# 02_ZYNQ_CORE_POS.net
KiCad netlist of a schematic drawn in Altium Designer
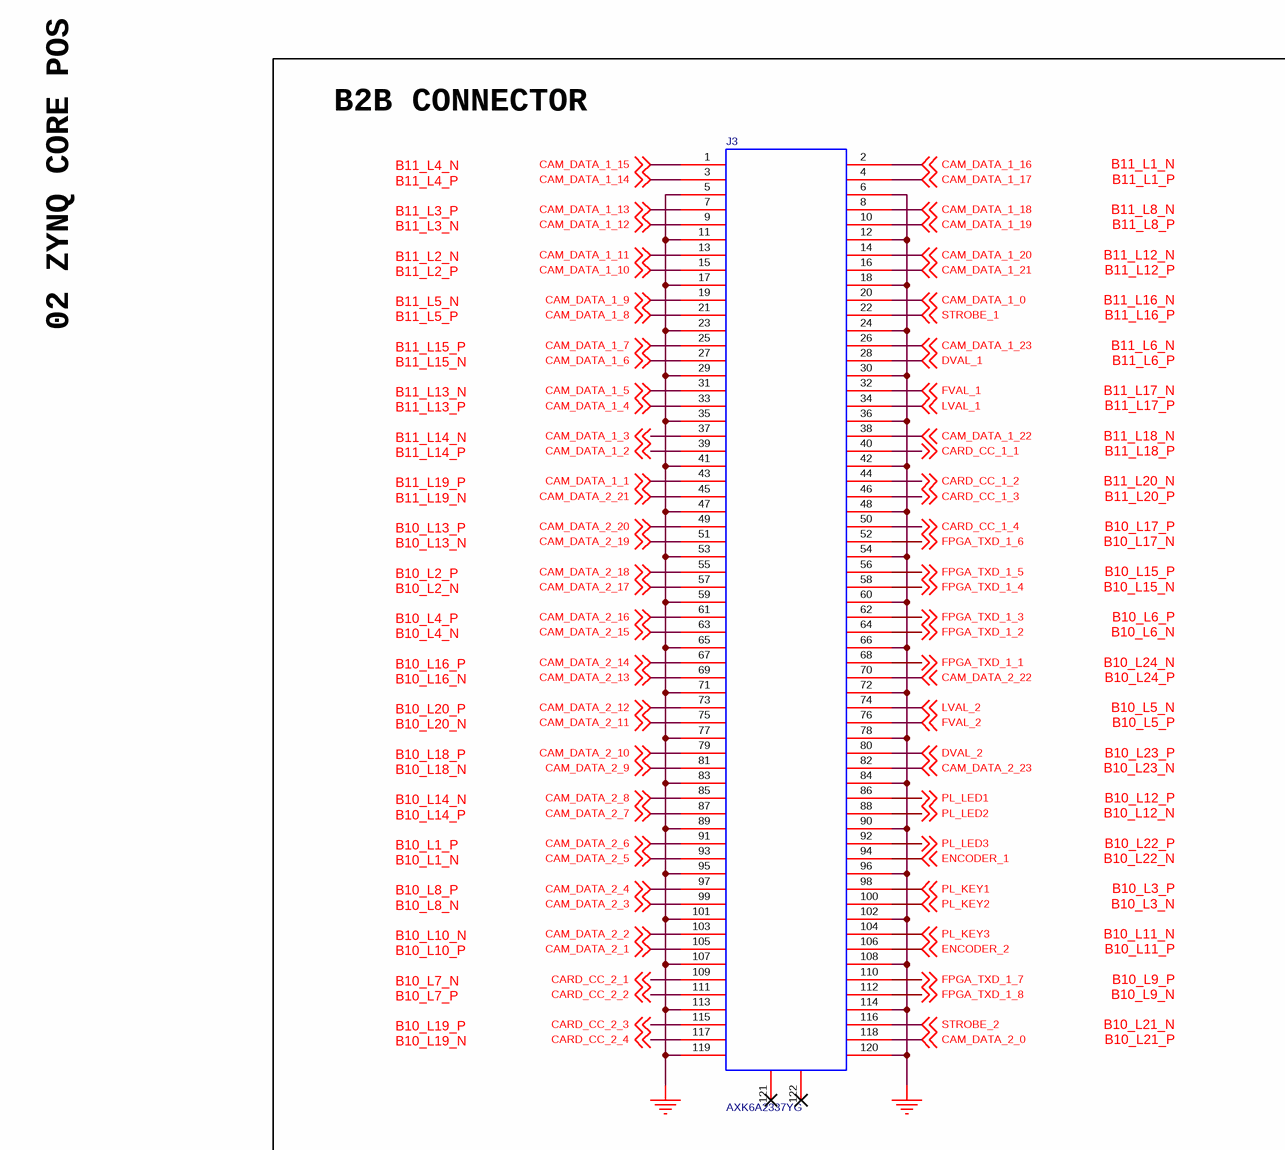
[diagram p0: 02_ZYNQ_CORE_POS.SchDoc, top left]
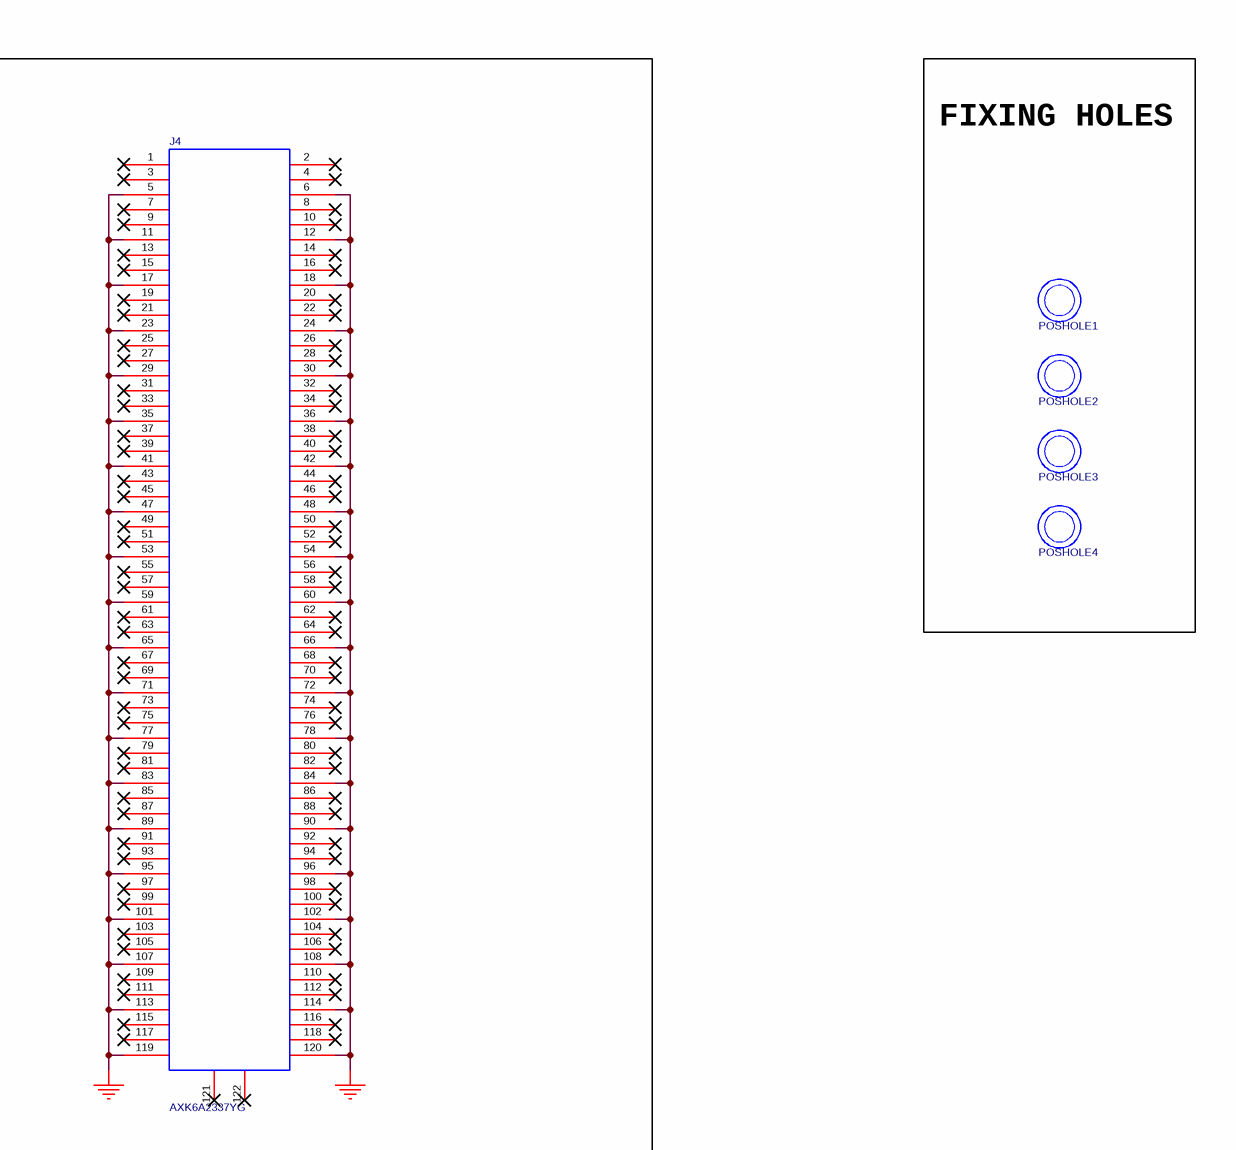
[diagram p1: 02_ZYNQ_CORE_POS.SchDoc, top right]
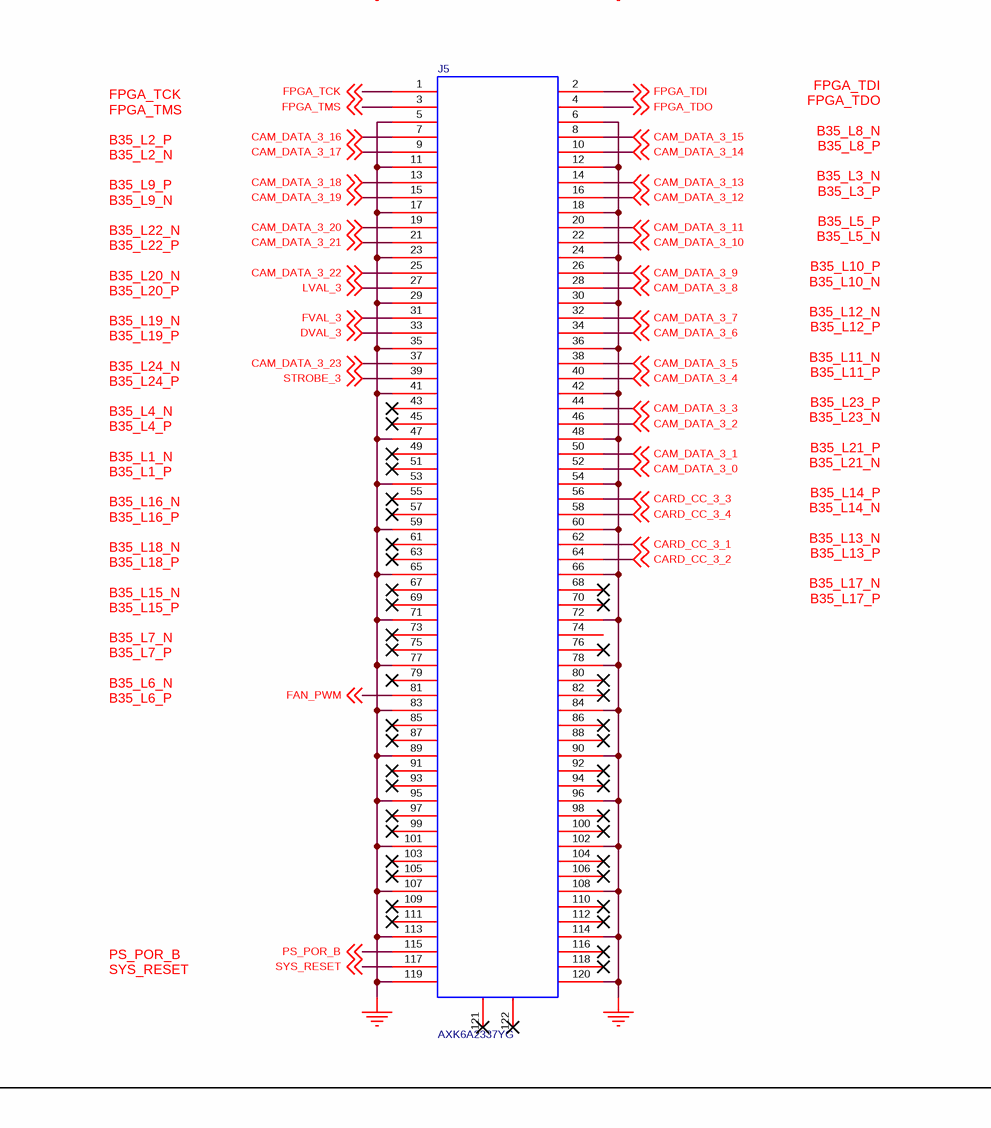
[diagram p2: 02_ZYNQ_CORE_POS.SchDoc, bottom left]
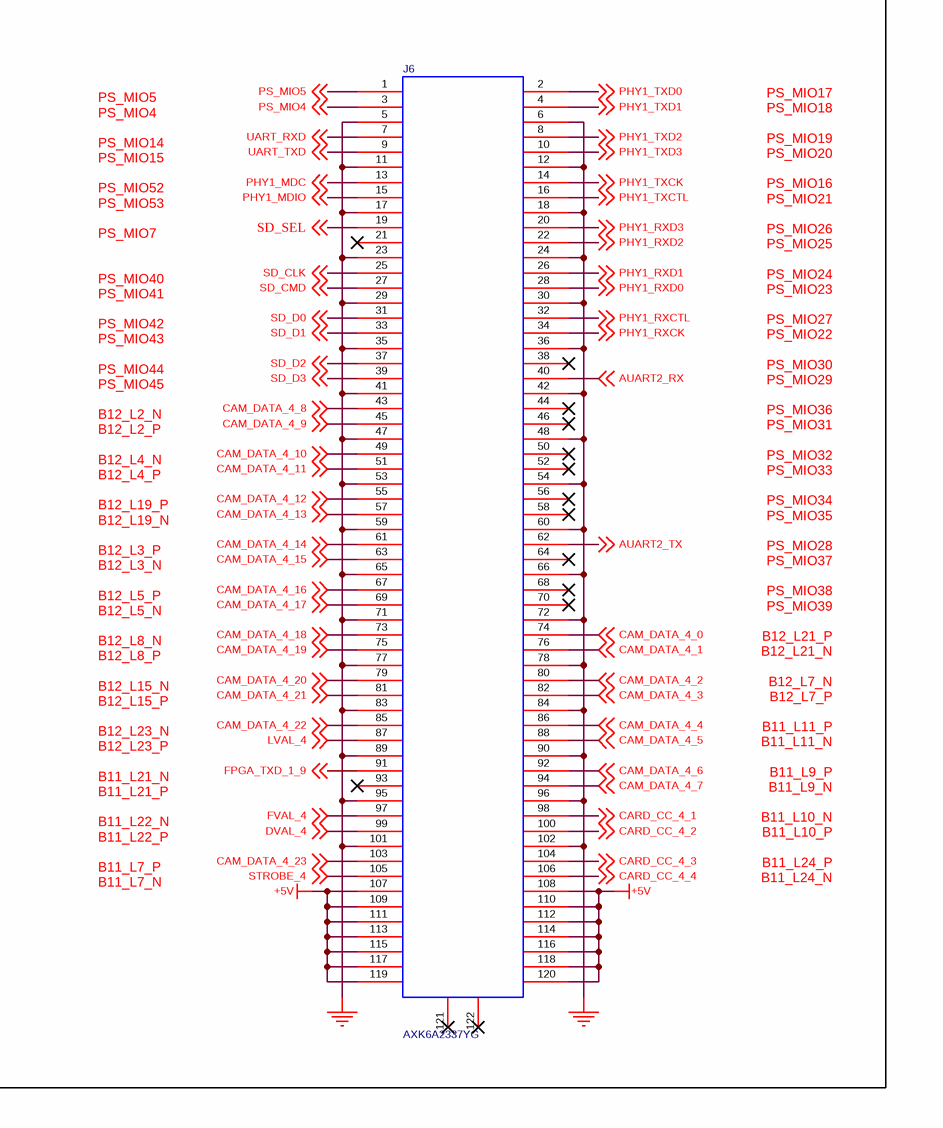
[diagram p3: 02_ZYNQ_CORE_POS.SchDoc, bottom right]

(export (version "E")
  (design (tool "Eeschema 10.0.6"))
  (components
    (comp (ref "J3")
      (value "AXK6A2337YG")
      (footprint "zynq:AXK620337YG")
      (libsource (lib "zynq") (part "120pin"))
    )
    (comp (ref "J4")
      (value "AXK6A2337YG")
      (footprint "zynq:AXK620337YG")
      (libsource (lib "zynq") (part "120pin"))
    )
    (comp (ref "J5")
      (value "AXK6A2337YG")
      (footprint "zynq:AXK620337YG")
      (libsource (lib "zynq") (part "120pin"))
    )
    (comp (ref "J6")
      (value "AXK6A2337YG")
      (footprint "zynq:AXK620337YG")
      (libsource (lib "zynq") (part "120pin"))
    )
    (comp (ref "POSHOLE1")
      (value "POSHOLE")
      (footprint "zynq:POSHOLE-3.2")
      (libsource (lib "zynq") (part "POSHOLE"))
    )
    (comp (ref "POSHOLE2")
      (value "POSHOLE")
      (footprint "zynq:POSHOLE-3.2")
      (libsource (lib "zynq") (part "POSHOLE"))
    )
    (comp (ref "POSHOLE3")
      (value "POSHOLE")
      (footprint "zynq:POSHOLE-3.2")
      (libsource (lib "zynq") (part "POSHOLE"))
    )
    (comp (ref "POSHOLE4")
      (value "POSHOLE")
      (footprint "zynq:POSHOLE-3.2")
      (libsource (lib "zynq") (part "POSHOLE"))
    )
  )
  (nets
    (net (code "1") (name "+5V") (class "Default")
      (node (ref "J6") (pin "107") (pintype "passive"))
      (node (ref "J6") (pin "108") (pintype "passive"))
      (node (ref "J6") (pin "109") (pintype "passive"))
      (node (ref "J6") (pin "110") (pintype "passive"))
      (node (ref "J6") (pin "111") (pintype "passive"))
      (node (ref "J6") (pin "112") (pintype "passive"))
      (node (ref "J6") (pin "113") (pintype "passive"))
      (node (ref "J6") (pin "114") (pintype "passive"))
      (node (ref "J6") (pin "115") (pintype "passive"))
      (node (ref "J6") (pin "116") (pintype "passive"))
      (node (ref "J6") (pin "117") (pintype "passive"))
      (node (ref "J6") (pin "118") (pintype "passive"))
      (node (ref "J6") (pin "119") (pintype "passive"))
      (node (ref "J6") (pin "120") (pintype "passive"))
    )
    (net (code "2") (name "AUART2_RX") (class "Default") (node (ref "J6") (pin "40") (pintype "passive")))
    (net (code "3") (name "AUART2_TX") (class "Default") (node (ref "J6") (pin "62") (pintype "passive")))
    (net (code "4") (name "CAM_DATA_1_0") (class "Default") (node (ref "J3") (pin "20") (pintype "passive")))
    (net (code "5") (name "CAM_DATA_1_1") (class "Default") (node (ref "J3") (pin "43") (pintype "passive")))
    (net (code "6") (name "CAM_DATA_1_2") (class "Default") (node (ref "J3") (pin "39") (pintype "passive")))
    (net (code "7") (name "CAM_DATA_1_3") (class "Default") (node (ref "J3") (pin "37") (pintype "passive")))
    (net (code "8") (name "CAM_DATA_1_4") (class "Default") (node (ref "J3") (pin "33") (pintype "passive")))
    (net (code "9") (name "CAM_DATA_1_5") (class "Default") (node (ref "J3") (pin "31") (pintype "passive")))
    (net (code "10") (name "CAM_DATA_1_6") (class "Default") (node (ref "J3") (pin "27") (pintype "passive")))
    (net (code "11") (name "CAM_DATA_1_7") (class "Default") (node (ref "J3") (pin "25") (pintype "passive")))
    (net (code "12") (name "CAM_DATA_1_8") (class "Default") (node (ref "J3") (pin "21") (pintype "passive")))
    (net (code "13") (name "CAM_DATA_1_9") (class "Default") (node (ref "J3") (pin "19") (pintype "passive")))
    (net (code "14") (name "CAM_DATA_1_10") (class "Default")
      (node (ref "J3") (pin "15") (pintype "passive"))
    )
    (net (code "15") (name "CAM_DATA_1_11") (class "Default")
      (node (ref "J3") (pin "13") (pintype "passive"))
    )
    (net (code "16") (name "CAM_DATA_1_12") (class "Default") (node (ref "J3") (pin "9") (pintype "passive")))
    (net (code "17") (name "CAM_DATA_1_13") (class "Default") (node (ref "J3") (pin "7") (pintype "passive")))
    (net (code "18") (name "CAM_DATA_1_14") (class "Default") (node (ref "J3") (pin "3") (pintype "passive")))
    (net (code "19") (name "CAM_DATA_1_15") (class "Default") (node (ref "J3") (pin "1") (pintype "passive")))
    (net (code "20") (name "CAM_DATA_1_16") (class "Default") (node (ref "J3") (pin "2") (pintype "passive")))
    (net (code "21") (name "CAM_DATA_1_17") (class "Default") (node (ref "J3") (pin "4") (pintype "passive")))
    (net (code "22") (name "CAM_DATA_1_18") (class "Default") (node (ref "J3") (pin "8") (pintype "passive")))
    (net (code "23") (name "CAM_DATA_1_19") (class "Default")
      (node (ref "J3") (pin "10") (pintype "passive"))
    )
    (net (code "24") (name "CAM_DATA_1_20") (class "Default")
      (node (ref "J3") (pin "14") (pintype "passive"))
    )
    (net (code "25") (name "CAM_DATA_1_21") (class "Default")
      (node (ref "J3") (pin "16") (pintype "passive"))
    )
    (net (code "26") (name "CAM_DATA_1_22") (class "Default")
      (node (ref "J3") (pin "38") (pintype "passive"))
    )
    (net (code "27") (name "CAM_DATA_1_23") (class "Default")
      (node (ref "J3") (pin "26") (pintype "passive"))
    )
    (net (code "28") (name "CAM_DATA_2_0") (class "Default")
      (node (ref "J3") (pin "118") (pintype "passive"))
    )
    (net (code "29") (name "CAM_DATA_2_1") (class "Default")
      (node (ref "J3") (pin "105") (pintype "passive"))
    )
    (net (code "30") (name "CAM_DATA_2_2") (class "Default")
      (node (ref "J3") (pin "103") (pintype "passive"))
    )
    (net (code "31") (name "CAM_DATA_2_3") (class "Default") (node (ref "J3") (pin "99") (pintype "passive")))
    (net (code "32") (name "CAM_DATA_2_4") (class "Default") (node (ref "J3") (pin "97") (pintype "passive")))
    (net (code "33") (name "CAM_DATA_2_5") (class "Default") (node (ref "J3") (pin "93") (pintype "passive")))
    (net (code "34") (name "CAM_DATA_2_6") (class "Default") (node (ref "J3") (pin "91") (pintype "passive")))
    (net (code "35") (name "CAM_DATA_2_7") (class "Default") (node (ref "J3") (pin "87") (pintype "passive")))
    (net (code "36") (name "CAM_DATA_2_8") (class "Default") (node (ref "J3") (pin "85") (pintype "passive")))
    (net (code "37") (name "CAM_DATA_2_9") (class "Default") (node (ref "J3") (pin "81") (pintype "passive")))
    (net (code "38") (name "CAM_DATA_2_10") (class "Default")
      (node (ref "J3") (pin "79") (pintype "passive"))
    )
    (net (code "39") (name "CAM_DATA_2_11") (class "Default")
      (node (ref "J3") (pin "75") (pintype "passive"))
    )
    (net (code "40") (name "CAM_DATA_2_12") (class "Default")
      (node (ref "J3") (pin "73") (pintype "passive"))
    )
    (net (code "41") (name "CAM_DATA_2_13") (class "Default")
      (node (ref "J3") (pin "69") (pintype "passive"))
    )
    (net (code "42") (name "CAM_DATA_2_14") (class "Default")
      (node (ref "J3") (pin "67") (pintype "passive"))
    )
    (net (code "43") (name "CAM_DATA_2_15") (class "Default")
      (node (ref "J3") (pin "63") (pintype "passive"))
    )
    (net (code "44") (name "CAM_DATA_2_16") (class "Default")
      (node (ref "J3") (pin "61") (pintype "passive"))
    )
    (net (code "45") (name "CAM_DATA_2_17") (class "Default")
      (node (ref "J3") (pin "57") (pintype "passive"))
    )
    (net (code "46") (name "CAM_DATA_2_18") (class "Default")
      (node (ref "J3") (pin "55") (pintype "passive"))
    )
    (net (code "47") (name "CAM_DATA_2_19") (class "Default")
      (node (ref "J3") (pin "51") (pintype "passive"))
    )
    (net (code "48") (name "CAM_DATA_2_20") (class "Default")
      (node (ref "J3") (pin "49") (pintype "passive"))
    )
    (net (code "49") (name "CAM_DATA_2_21") (class "Default")
      (node (ref "J3") (pin "45") (pintype "passive"))
    )
    (net (code "50") (name "CAM_DATA_2_22") (class "Default")
      (node (ref "J3") (pin "70") (pintype "passive"))
    )
    (net (code "51") (name "CAM_DATA_2_23") (class "Default")
      (node (ref "J3") (pin "82") (pintype "passive"))
    )
    (net (code "52") (name "CAM_DATA_3_0") (class "Default") (node (ref "J5") (pin "52") (pintype "passive")))
    (net (code "53") (name "CAM_DATA_3_1") (class "Default") (node (ref "J5") (pin "50") (pintype "passive")))
    (net (code "54") (name "CAM_DATA_3_2") (class "Default") (node (ref "J5") (pin "46") (pintype "passive")))
    (net (code "55") (name "CAM_DATA_3_3") (class "Default") (node (ref "J5") (pin "44") (pintype "passive")))
    (net (code "56") (name "CAM_DATA_3_4") (class "Default") (node (ref "J5") (pin "40") (pintype "passive")))
    (net (code "57") (name "CAM_DATA_3_5") (class "Default") (node (ref "J5") (pin "38") (pintype "passive")))
    (net (code "58") (name "CAM_DATA_3_6") (class "Default") (node (ref "J5") (pin "34") (pintype "passive")))
    (net (code "59") (name "CAM_DATA_3_7") (class "Default") (node (ref "J5") (pin "32") (pintype "passive")))
    (net (code "60") (name "CAM_DATA_3_8") (class "Default") (node (ref "J5") (pin "28") (pintype "passive")))
    (net (code "61") (name "CAM_DATA_3_9") (class "Default") (node (ref "J5") (pin "26") (pintype "passive")))
    (net (code "62") (name "CAM_DATA_3_10") (class "Default")
      (node (ref "J5") (pin "22") (pintype "passive"))
    )
    (net (code "63") (name "CAM_DATA_3_11") (class "Default")
      (node (ref "J5") (pin "20") (pintype "passive"))
    )
    (net (code "64") (name "CAM_DATA_3_12") (class "Default")
      (node (ref "J5") (pin "16") (pintype "passive"))
    )
    (net (code "65") (name "CAM_DATA_3_13") (class "Default")
      (node (ref "J5") (pin "14") (pintype "passive"))
    )
    (net (code "66") (name "CAM_DATA_3_14") (class "Default")
      (node (ref "J5") (pin "10") (pintype "passive"))
    )
    (net (code "67") (name "CAM_DATA_3_15") (class "Default") (node (ref "J5") (pin "8") (pintype "passive")))
    (net (code "68") (name "CAM_DATA_3_16") (class "Default") (node (ref "J5") (pin "7") (pintype "passive")))
    (net (code "69") (name "CAM_DATA_3_17") (class "Default") (node (ref "J5") (pin "9") (pintype "passive")))
    (net (code "70") (name "CAM_DATA_3_18") (class "Default")
      (node (ref "J5") (pin "13") (pintype "passive"))
    )
    (net (code "71") (name "CAM_DATA_3_19") (class "Default")
      (node (ref "J5") (pin "15") (pintype "passive"))
    )
    (net (code "72") (name "CAM_DATA_3_20") (class "Default")
      (node (ref "J5") (pin "19") (pintype "passive"))
    )
    (net (code "73") (name "CAM_DATA_3_21") (class "Default")
      (node (ref "J5") (pin "21") (pintype "passive"))
    )
    (net (code "74") (name "CAM_DATA_3_22") (class "Default")
      (node (ref "J5") (pin "25") (pintype "passive"))
    )
    (net (code "75") (name "CAM_DATA_3_23") (class "Default")
      (node (ref "J5") (pin "37") (pintype "passive"))
    )
    (net (code "76") (name "CAM_DATA_4_0") (class "Default") (node (ref "J6") (pin "74") (pintype "passive")))
    (net (code "77") (name "CAM_DATA_4_1") (class "Default") (node (ref "J6") (pin "76") (pintype "passive")))
    (net (code "78") (name "CAM_DATA_4_2") (class "Default") (node (ref "J6") (pin "80") (pintype "passive")))
    (net (code "79") (name "CAM_DATA_4_3") (class "Default") (node (ref "J6") (pin "82") (pintype "passive")))
    (net (code "80") (name "CAM_DATA_4_4") (class "Default") (node (ref "J6") (pin "86") (pintype "passive")))
    (net (code "81") (name "CAM_DATA_4_5") (class "Default") (node (ref "J6") (pin "88") (pintype "passive")))
    (net (code "82") (name "CAM_DATA_4_6") (class "Default") (node (ref "J6") (pin "92") (pintype "passive")))
    (net (code "83") (name "CAM_DATA_4_7") (class "Default") (node (ref "J6") (pin "94") (pintype "passive")))
    (net (code "84") (name "CAM_DATA_4_8") (class "Default") (node (ref "J6") (pin "43") (pintype "passive")))
    (net (code "85") (name "CAM_DATA_4_9") (class "Default") (node (ref "J6") (pin "45") (pintype "passive")))
    (net (code "86") (name "CAM_DATA_4_10") (class "Default")
      (node (ref "J6") (pin "49") (pintype "passive"))
    )
    (net (code "87") (name "CAM_DATA_4_11") (class "Default")
      (node (ref "J6") (pin "51") (pintype "passive"))
    )
    (net (code "88") (name "CAM_DATA_4_12") (class "Default")
      (node (ref "J6") (pin "55") (pintype "passive"))
    )
    (net (code "89") (name "CAM_DATA_4_13") (class "Default")
      (node (ref "J6") (pin "57") (pintype "passive"))
    )
    (net (code "90") (name "CAM_DATA_4_14") (class "Default")
      (node (ref "J6") (pin "61") (pintype "passive"))
    )
    (net (code "91") (name "CAM_DATA_4_15") (class "Default")
      (node (ref "J6") (pin "63") (pintype "passive"))
    )
    (net (code "92") (name "CAM_DATA_4_16") (class "Default")
      (node (ref "J6") (pin "67") (pintype "passive"))
    )
    (net (code "93") (name "CAM_DATA_4_17") (class "Default")
      (node (ref "J6") (pin "69") (pintype "passive"))
    )
    (net (code "94") (name "CAM_DATA_4_18") (class "Default")
      (node (ref "J6") (pin "73") (pintype "passive"))
    )
    (net (code "95") (name "CAM_DATA_4_19") (class "Default")
      (node (ref "J6") (pin "75") (pintype "passive"))
    )
    (net (code "96") (name "CAM_DATA_4_20") (class "Default")
      (node (ref "J6") (pin "79") (pintype "passive"))
    )
    (net (code "97") (name "CAM_DATA_4_21") (class "Default")
      (node (ref "J6") (pin "81") (pintype "passive"))
    )
    (net (code "98") (name "CAM_DATA_4_22") (class "Default")
      (node (ref "J6") (pin "85") (pintype "passive"))
    )
    (net (code "99") (name "CAM_DATA_4_23") (class "Default")
      (node (ref "J6") (pin "103") (pintype "passive"))
    )
    (net (code "100") (name "CARD_CC_1_1") (class "Default") (node (ref "J3") (pin "40") (pintype "passive")))
    (net (code "101") (name "CARD_CC_1_2") (class "Default") (node (ref "J3") (pin "44") (pintype "passive")))
    (net (code "102") (name "CARD_CC_1_3") (class "Default") (node (ref "J3") (pin "46") (pintype "passive")))
    (net (code "103") (name "CARD_CC_1_4") (class "Default") (node (ref "J3") (pin "50") (pintype "passive")))
    (net (code "104") (name "CARD_CC_2_1") (class "Default")
      (node (ref "J3") (pin "109") (pintype "passive"))
    )
    (net (code "105") (name "CARD_CC_2_2") (class "Default")
      (node (ref "J3") (pin "111") (pintype "passive"))
    )
    (net (code "106") (name "CARD_CC_2_3") (class "Default")
      (node (ref "J3") (pin "115") (pintype "passive"))
    )
    (net (code "107") (name "CARD_CC_2_4") (class "Default")
      (node (ref "J3") (pin "117") (pintype "passive"))
    )
    (net (code "108") (name "CARD_CC_3_1") (class "Default") (node (ref "J5") (pin "62") (pintype "passive")))
    (net (code "109") (name "CARD_CC_3_2") (class "Default") (node (ref "J5") (pin "64") (pintype "passive")))
    (net (code "110") (name "CARD_CC_3_3") (class "Default") (node (ref "J5") (pin "56") (pintype "passive")))
    (net (code "111") (name "CARD_CC_3_4") (class "Default") (node (ref "J5") (pin "58") (pintype "passive")))
    (net (code "112") (name "CARD_CC_4_1") (class "Default") (node (ref "J6") (pin "98") (pintype "passive")))
    (net (code "113") (name "CARD_CC_4_2") (class "Default")
      (node (ref "J6") (pin "100") (pintype "passive"))
    )
    (net (code "114") (name "CARD_CC_4_3") (class "Default")
      (node (ref "J6") (pin "104") (pintype "passive"))
    )
    (net (code "115") (name "CARD_CC_4_4") (class "Default")
      (node (ref "J6") (pin "106") (pintype "passive"))
    )
    (net (code "116") (name "DVAL_1") (class "Default") (node (ref "J3") (pin "28") (pintype "passive")))
    (net (code "117") (name "DVAL_2") (class "Default") (node (ref "J3") (pin "80") (pintype "passive")))
    (net (code "118") (name "DVAL_3") (class "Default") (node (ref "J5") (pin "33") (pintype "passive")))
    (net (code "119") (name "DVAL_4") (class "Default") (node (ref "J6") (pin "99") (pintype "passive")))
    (net (code "120") (name "ENCODER_1") (class "Default") (node (ref "J3") (pin "94") (pintype "passive")))
    (net (code "121") (name "ENCODER_2") (class "Default") (node (ref "J3") (pin "106") (pintype "passive")))
    (net (code "122") (name "FAN_PWM") (class "Default") (node (ref "J5") (pin "81") (pintype "passive")))
    (net (code "123") (name "FPGA_TCK") (class "Default") (node (ref "J5") (pin "1") (pintype "passive")))
    (net (code "124") (name "FPGA_TDI") (class "Default") (node (ref "J5") (pin "2") (pintype "passive")))
    (net (code "125") (name "FPGA_TDO") (class "Default") (node (ref "J5") (pin "4") (pintype "passive")))
    (net (code "126") (name "FPGA_TMS") (class "Default") (node (ref "J5") (pin "3") (pintype "passive")))
    (net (code "127") (name "FPGA_TXD_1_1") (class "Default")
      (node (ref "J3") (pin "68") (pintype "passive"))
    )
    (net (code "128") (name "FPGA_TXD_1_2") (class "Default")
      (node (ref "J3") (pin "64") (pintype "passive"))
    )
    (net (code "129") (name "FPGA_TXD_1_3") (class "Default")
      (node (ref "J3") (pin "62") (pintype "passive"))
    )
    (net (code "130") (name "FPGA_TXD_1_4") (class "Default")
      (node (ref "J3") (pin "58") (pintype "passive"))
    )
    (net (code "131") (name "FPGA_TXD_1_5") (class "Default")
      (node (ref "J3") (pin "56") (pintype "passive"))
    )
    (net (code "132") (name "FPGA_TXD_1_6") (class "Default")
      (node (ref "J3") (pin "52") (pintype "passive"))
    )
    (net (code "133") (name "FPGA_TXD_1_7") (class "Default")
      (node (ref "J3") (pin "110") (pintype "passive"))
    )
    (net (code "134") (name "FPGA_TXD_1_8") (class "Default")
      (node (ref "J3") (pin "112") (pintype "passive"))
    )
    (net (code "135") (name "FPGA_TXD_1_9") (class "Default")
      (node (ref "J6") (pin "91") (pintype "passive"))
    )
    (net (code "136") (name "FVAL_1") (class "Default") (node (ref "J3") (pin "32") (pintype "passive")))
    (net (code "137") (name "FVAL_2") (class "Default") (node (ref "J3") (pin "76") (pintype "passive")))
    (net (code "138") (name "FVAL_3") (class "Default") (node (ref "J5") (pin "31") (pintype "passive")))
    (net (code "139") (name "FVAL_4") (class "Default") (node (ref "J6") (pin "97") (pintype "passive")))
    (net (code "140") (name "GND") (class "Default")
      (node (ref "J3") (pin "101") (pintype "passive"))
      (node (ref "J3") (pin "102") (pintype "passive"))
      (node (ref "J3") (pin "107") (pintype "passive"))
      (node (ref "J3") (pin "108") (pintype "passive"))
      (node (ref "J3") (pin "11") (pintype "passive"))
      (node (ref "J3") (pin "113") (pintype "passive"))
      (node (ref "J3") (pin "114") (pintype "passive"))
      (node (ref "J3") (pin "119") (pintype "passive"))
      (node (ref "J3") (pin "12") (pintype "passive"))
      (node (ref "J3") (pin "120") (pintype "passive"))
      (node (ref "J3") (pin "17") (pintype "passive"))
      (node (ref "J3") (pin "18") (pintype "passive"))
      (node (ref "J3") (pin "23") (pintype "passive"))
      (node (ref "J3") (pin "24") (pintype "passive"))
      (node (ref "J3") (pin "29") (pintype "passive"))
      (node (ref "J3") (pin "30") (pintype "passive"))
      (node (ref "J3") (pin "35") (pintype "passive"))
      (node (ref "J3") (pin "36") (pintype "passive"))
      (node (ref "J3") (pin "41") (pintype "passive"))
      (node (ref "J3") (pin "42") (pintype "passive"))
      (node (ref "J3") (pin "47") (pintype "passive"))
      (node (ref "J3") (pin "48") (pintype "passive"))
      (node (ref "J3") (pin "5") (pintype "passive"))
      (node (ref "J3") (pin "53") (pintype "passive"))
      (node (ref "J3") (pin "54") (pintype "passive"))
      (node (ref "J3") (pin "59") (pintype "passive"))
      (node (ref "J3") (pin "6") (pintype "passive"))
      (node (ref "J3") (pin "60") (pintype "passive"))
      (node (ref "J3") (pin "65") (pintype "passive"))
      (node (ref "J3") (pin "66") (pintype "passive"))
      (node (ref "J3") (pin "71") (pintype "passive"))
      (node (ref "J3") (pin "72") (pintype "passive"))
      (node (ref "J3") (pin "77") (pintype "passive"))
      (node (ref "J3") (pin "78") (pintype "passive"))
      (node (ref "J3") (pin "83") (pintype "passive"))
      (node (ref "J3") (pin "84") (pintype "passive"))
      (node (ref "J3") (pin "89") (pintype "passive"))
      (node (ref "J3") (pin "90") (pintype "passive"))
      (node (ref "J3") (pin "95") (pintype "passive"))
      (node (ref "J3") (pin "96") (pintype "passive"))
      (node (ref "J4") (pin "101") (pintype "passive"))
      (node (ref "J4") (pin "102") (pintype "passive"))
      (node (ref "J4") (pin "107") (pintype "passive"))
      (node (ref "J4") (pin "108") (pintype "passive"))
      (node (ref "J4") (pin "11") (pintype "passive"))
      (node (ref "J4") (pin "113") (pintype "passive"))
      (node (ref "J4") (pin "114") (pintype "passive"))
      (node (ref "J4") (pin "119") (pintype "passive"))
      (node (ref "J4") (pin "12") (pintype "passive"))
      (node (ref "J4") (pin "120") (pintype "passive"))
      (node (ref "J4") (pin "17") (pintype "passive"))
      (node (ref "J4") (pin "18") (pintype "passive"))
      (node (ref "J4") (pin "23") (pintype "passive"))
      (node (ref "J4") (pin "24") (pintype "passive"))
      (node (ref "J4") (pin "29") (pintype "passive"))
      (node (ref "J4") (pin "30") (pintype "passive"))
      (node (ref "J4") (pin "35") (pintype "passive"))
      (node (ref "J4") (pin "36") (pintype "passive"))
      (node (ref "J4") (pin "41") (pintype "passive"))
      (node (ref "J4") (pin "42") (pintype "passive"))
      (node (ref "J4") (pin "47") (pintype "passive"))
      (node (ref "J4") (pin "48") (pintype "passive"))
      (node (ref "J4") (pin "5") (pintype "passive"))
      (node (ref "J4") (pin "53") (pintype "passive"))
      (node (ref "J4") (pin "54") (pintype "passive"))
      (node (ref "J4") (pin "59") (pintype "passive"))
      (node (ref "J4") (pin "6") (pintype "passive"))
      (node (ref "J4") (pin "60") (pintype "passive"))
      (node (ref "J4") (pin "65") (pintype "passive"))
      (node (ref "J4") (pin "66") (pintype "passive"))
      (node (ref "J4") (pin "71") (pintype "passive"))
      (node (ref "J4") (pin "72") (pintype "passive"))
      (node (ref "J4") (pin "77") (pintype "passive"))
      (node (ref "J4") (pin "78") (pintype "passive"))
      (node (ref "J4") (pin "83") (pintype "passive"))
      (node (ref "J4") (pin "84") (pintype "passive"))
      (node (ref "J4") (pin "89") (pintype "passive"))
      (node (ref "J4") (pin "90") (pintype "passive"))
      (node (ref "J4") (pin "95") (pintype "passive"))
      (node (ref "J4") (pin "96") (pintype "passive"))
      (node (ref "J5") (pin "101") (pintype "passive"))
      (node (ref "J5") (pin "102") (pintype "passive"))
      (node (ref "J5") (pin "107") (pintype "passive"))
      (node (ref "J5") (pin "108") (pintype "passive"))
      (node (ref "J5") (pin "11") (pintype "passive"))
      (node (ref "J5") (pin "113") (pintype "passive"))
      (node (ref "J5") (pin "114") (pintype "passive"))
      (node (ref "J5") (pin "119") (pintype "passive"))
      (node (ref "J5") (pin "12") (pintype "passive"))
      (node (ref "J5") (pin "120") (pintype "passive"))
      (node (ref "J5") (pin "17") (pintype "passive"))
      (node (ref "J5") (pin "18") (pintype "passive"))
      (node (ref "J5") (pin "23") (pintype "passive"))
      (node (ref "J5") (pin "24") (pintype "passive"))
      (node (ref "J5") (pin "29") (pintype "passive"))
      (node (ref "J5") (pin "30") (pintype "passive"))
      (node (ref "J5") (pin "35") (pintype "passive"))
      (node (ref "J5") (pin "36") (pintype "passive"))
      (node (ref "J5") (pin "41") (pintype "passive"))
      (node (ref "J5") (pin "42") (pintype "passive"))
      (node (ref "J5") (pin "47") (pintype "passive"))
      (node (ref "J5") (pin "48") (pintype "passive"))
      (node (ref "J5") (pin "5") (pintype "passive"))
      (node (ref "J5") (pin "53") (pintype "passive"))
      (node (ref "J5") (pin "54") (pintype "passive"))
      (node (ref "J5") (pin "59") (pintype "passive"))
      (node (ref "J5") (pin "6") (pintype "passive"))
      (node (ref "J5") (pin "60") (pintype "passive"))
      (node (ref "J5") (pin "65") (pintype "passive"))
      (node (ref "J5") (pin "66") (pintype "passive"))
      (node (ref "J5") (pin "71") (pintype "passive"))
      (node (ref "J5") (pin "72") (pintype "passive"))
      (node (ref "J5") (pin "77") (pintype "passive"))
      (node (ref "J5") (pin "78") (pintype "passive"))
      (node (ref "J5") (pin "83") (pintype "passive"))
      (node (ref "J5") (pin "84") (pintype "passive"))
      (node (ref "J5") (pin "89") (pintype "passive"))
      (node (ref "J5") (pin "90") (pintype "passive"))
      (node (ref "J5") (pin "95") (pintype "passive"))
      (node (ref "J5") (pin "96") (pintype "passive"))
      (node (ref "J6") (pin "101") (pintype "passive"))
      (node (ref "J6") (pin "102") (pintype "passive"))
      (node (ref "J6") (pin "11") (pintype "passive"))
      (node (ref "J6") (pin "12") (pintype "passive"))
      (node (ref "J6") (pin "17") (pintype "passive"))
      (node (ref "J6") (pin "18") (pintype "passive"))
      (node (ref "J6") (pin "23") (pintype "passive"))
      (node (ref "J6") (pin "24") (pintype "passive"))
      (node (ref "J6") (pin "29") (pintype "passive"))
      (node (ref "J6") (pin "30") (pintype "passive"))
      (node (ref "J6") (pin "35") (pintype "passive"))
      (node (ref "J6") (pin "36") (pintype "passive"))
      (node (ref "J6") (pin "41") (pintype "passive"))
      (node (ref "J6") (pin "42") (pintype "passive"))
      (node (ref "J6") (pin "47") (pintype "passive"))
      (node (ref "J6") (pin "48") (pintype "passive"))
      (node (ref "J6") (pin "5") (pintype "passive"))
      (node (ref "J6") (pin "53") (pintype "passive"))
      (node (ref "J6") (pin "54") (pintype "passive"))
      (node (ref "J6") (pin "59") (pintype "passive"))
      (node (ref "J6") (pin "6") (pintype "passive"))
      (node (ref "J6") (pin "60") (pintype "passive"))
      (node (ref "J6") (pin "65") (pintype "passive"))
      (node (ref "J6") (pin "66") (pintype "passive"))
      (node (ref "J6") (pin "71") (pintype "passive"))
      (node (ref "J6") (pin "72") (pintype "passive"))
      (node (ref "J6") (pin "77") (pintype "passive"))
      (node (ref "J6") (pin "78") (pintype "passive"))
      (node (ref "J6") (pin "83") (pintype "passive"))
      (node (ref "J6") (pin "84") (pintype "passive"))
      (node (ref "J6") (pin "89") (pintype "passive"))
      (node (ref "J6") (pin "90") (pintype "passive"))
      (node (ref "J6") (pin "95") (pintype "passive"))
      (node (ref "J6") (pin "96") (pintype "passive"))
    )
    (net (code "141") (name "LVAL_1") (class "Default") (node (ref "J3") (pin "34") (pintype "passive")))
    (net (code "142") (name "LVAL_2") (class "Default") (node (ref "J3") (pin "74") (pintype "passive")))
    (net (code "143") (name "LVAL_3") (class "Default") (node (ref "J5") (pin "27") (pintype "passive")))
    (net (code "144") (name "LVAL_4") (class "Default") (node (ref "J6") (pin "87") (pintype "passive")))
    (net (code "145") (name "PHY1_MDC") (class "Default") (node (ref "J6") (pin "13") (pintype "passive")))
    (net (code "146") (name "PHY1_MDIO") (class "Default") (node (ref "J6") (pin "15") (pintype "passive")))
    (net (code "147") (name "PHY1_RXCK") (class "Default") (node (ref "J6") (pin "34") (pintype "passive")))
    (net (code "148") (name "PHY1_RXCTL") (class "Default") (node (ref "J6") (pin "32") (pintype "passive")))
    (net (code "149") (name "PHY1_RXD0") (class "Default") (node (ref "J6") (pin "28") (pintype "passive")))
    (net (code "150") (name "PHY1_RXD1") (class "Default") (node (ref "J6") (pin "26") (pintype "passive")))
    (net (code "151") (name "PHY1_RXD2") (class "Default") (node (ref "J6") (pin "22") (pintype "passive")))
    (net (code "152") (name "PHY1_RXD3") (class "Default") (node (ref "J6") (pin "20") (pintype "passive")))
    (net (code "153") (name "PHY1_TXCK") (class "Default") (node (ref "J6") (pin "14") (pintype "passive")))
    (net (code "154") (name "PHY1_TXCTL") (class "Default") (node (ref "J6") (pin "16") (pintype "passive")))
    (net (code "155") (name "PHY1_TXD0") (class "Default") (node (ref "J6") (pin "2") (pintype "passive")))
    (net (code "156") (name "PHY1_TXD1") (class "Default") (node (ref "J6") (pin "4") (pintype "passive")))
    (net (code "157") (name "PHY1_TXD2") (class "Default") (node (ref "J6") (pin "8") (pintype "passive")))
    (net (code "158") (name "PHY1_TXD3") (class "Default") (node (ref "J6") (pin "10") (pintype "passive")))
    (net (code "159") (name "PL_KEY1") (class "Default") (node (ref "J3") (pin "98") (pintype "passive")))
    (net (code "160") (name "PL_KEY2") (class "Default") (node (ref "J3") (pin "100") (pintype "passive")))
    (net (code "161") (name "PL_KEY3") (class "Default") (node (ref "J3") (pin "104") (pintype "passive")))
    (net (code "162") (name "PL_LED1") (class "Default") (node (ref "J3") (pin "86") (pintype "passive")))
    (net (code "163") (name "PL_LED2") (class "Default") (node (ref "J3") (pin "88") (pintype "passive")))
    (net (code "164") (name "PL_LED3") (class "Default") (node (ref "J3") (pin "92") (pintype "passive")))
    (net (code "165") (name "PS_MIO4") (class "Default") (node (ref "J6") (pin "3") (pintype "passive")))
    (net (code "166") (name "PS_MIO5") (class "Default") (node (ref "J6") (pin "1") (pintype "passive")))
    (net (code "167") (name "PS_POR_B") (class "Default") (node (ref "J5") (pin "115") (pintype "passive")))
    (net (code "168") (name "SD_CLK") (class "Default") (node (ref "J6") (pin "25") (pintype "passive")))
    (net (code "169") (name "SD_CMD") (class "Default") (node (ref "J6") (pin "27") (pintype "passive")))
    (net (code "170") (name "SD_D0") (class "Default") (node (ref "J6") (pin "31") (pintype "passive")))
    (net (code "171") (name "SD_D1") (class "Default") (node (ref "J6") (pin "33") (pintype "passive")))
    (net (code "172") (name "SD_D2") (class "Default") (node (ref "J6") (pin "37") (pintype "passive")))
    (net (code "173") (name "SD_D3") (class "Default") (node (ref "J6") (pin "39") (pintype "passive")))
    (net (code "174") (name "SD_SEL") (class "Default") (node (ref "J6") (pin "19") (pintype "passive")))
    (net (code "175") (name "STROBE_1") (class "Default") (node (ref "J3") (pin "22") (pintype "passive")))
    (net (code "176") (name "STROBE_2") (class "Default") (node (ref "J3") (pin "116") (pintype "passive")))
    (net (code "177") (name "STROBE_3") (class "Default") (node (ref "J5") (pin "39") (pintype "passive")))
    (net (code "178") (name "STROBE_4") (class "Default") (node (ref "J6") (pin "105") (pintype "passive")))
    (net (code "179") (name "SYS_RESET") (class "Default") (node (ref "J5") (pin "117") (pintype "passive")))
    (net (code "180") (name "UART_RXD") (class "Default") (node (ref "J6") (pin "7") (pintype "passive")))
    (net (code "181") (name "UART_TXD") (class "Default") (node (ref "J6") (pin "9") (pintype "passive")))
    (net (code "182") (name "unconnected-(J3-Pad121)") (class "Default")
      (node (ref "J3") (pin "121") (pintype "passive+no_connect"))
    )
    (net (code "183") (name "unconnected-(J3-Pad122)") (class "Default")
      (node (ref "J3") (pin "122") (pintype "passive+no_connect"))
    )
    (net (code "184") (name "unconnected-(J4-Pad1)") (class "Default")
      (node (ref "J4") (pin "1") (pintype "passive+no_connect"))
    )
    (net (code "185") (name "unconnected-(J4-Pad2)") (class "Default")
      (node (ref "J4") (pin "2") (pintype "passive+no_connect"))
    )
    (net (code "186") (name "unconnected-(J4-Pad3)") (class "Default")
      (node (ref "J4") (pin "3") (pintype "passive+no_connect"))
    )
    (net (code "187") (name "unconnected-(J4-Pad4)") (class "Default")
      (node (ref "J4") (pin "4") (pintype "passive+no_connect"))
    )
    (net (code "188") (name "unconnected-(J4-Pad7)") (class "Default")
      (node (ref "J4") (pin "7") (pintype "passive+no_connect"))
    )
    (net (code "189") (name "unconnected-(J4-Pad8)") (class "Default")
      (node (ref "J4") (pin "8") (pintype "passive+no_connect"))
    )
    (net (code "190") (name "unconnected-(J4-Pad9)") (class "Default")
      (node (ref "J4") (pin "9") (pintype "passive+no_connect"))
    )
    (net (code "191") (name "unconnected-(J4-Pad10)") (class "Default")
      (node (ref "J4") (pin "10") (pintype "passive+no_connect"))
    )
    (net (code "192") (name "unconnected-(J4-Pad13)") (class "Default")
      (node (ref "J4") (pin "13") (pintype "passive+no_connect"))
    )
    (net (code "193") (name "unconnected-(J4-Pad14)") (class "Default")
      (node (ref "J4") (pin "14") (pintype "passive+no_connect"))
    )
    (net (code "194") (name "unconnected-(J4-Pad15)") (class "Default")
      (node (ref "J4") (pin "15") (pintype "passive+no_connect"))
    )
    (net (code "195") (name "unconnected-(J4-Pad16)") (class "Default")
      (node (ref "J4") (pin "16") (pintype "passive+no_connect"))
    )
    (net (code "196") (name "unconnected-(J4-Pad19)") (class "Default")
      (node (ref "J4") (pin "19") (pintype "passive+no_connect"))
    )
    (net (code "197") (name "unconnected-(J4-Pad20)") (class "Default")
      (node (ref "J4") (pin "20") (pintype "passive+no_connect"))
    )
    (net (code "198") (name "unconnected-(J4-Pad21)") (class "Default")
      (node (ref "J4") (pin "21") (pintype "passive+no_connect"))
    )
    (net (code "199") (name "unconnected-(J4-Pad22)") (class "Default")
      (node (ref "J4") (pin "22") (pintype "passive+no_connect"))
    )
    (net (code "200") (name "unconnected-(J4-Pad25)") (class "Default")
      (node (ref "J4") (pin "25") (pintype "passive+no_connect"))
    )
    (net (code "201") (name "unconnected-(J4-Pad26)") (class "Default")
      (node (ref "J4") (pin "26") (pintype "passive+no_connect"))
    )
    (net (code "202") (name "unconnected-(J4-Pad27)") (class "Default")
      (node (ref "J4") (pin "27") (pintype "passive+no_connect"))
    )
    (net (code "203") (name "unconnected-(J4-Pad28)") (class "Default")
      (node (ref "J4") (pin "28") (pintype "passive+no_connect"))
    )
    (net (code "204") (name "unconnected-(J4-Pad31)") (class "Default")
      (node (ref "J4") (pin "31") (pintype "passive+no_connect"))
    )
    (net (code "205") (name "unconnected-(J4-Pad32)") (class "Default")
      (node (ref "J4") (pin "32") (pintype "passive+no_connect"))
    )
    (net (code "206") (name "unconnected-(J4-Pad33)") (class "Default")
      (node (ref "J4") (pin "33") (pintype "passive+no_connect"))
    )
    (net (code "207") (name "unconnected-(J4-Pad34)") (class "Default")
      (node (ref "J4") (pin "34") (pintype "passive+no_connect"))
    )
    (net (code "208") (name "unconnected-(J4-Pad37)") (class "Default")
      (node (ref "J4") (pin "37") (pintype "passive+no_connect"))
    )
    (net (code "209") (name "unconnected-(J4-Pad38)") (class "Default")
      (node (ref "J4") (pin "38") (pintype "passive+no_connect"))
    )
    (net (code "210") (name "unconnected-(J4-Pad39)") (class "Default")
      (node (ref "J4") (pin "39") (pintype "passive+no_connect"))
    )
    (net (code "211") (name "unconnected-(J4-Pad40)") (class "Default")
      (node (ref "J4") (pin "40") (pintype "passive+no_connect"))
    )
    (net (code "212") (name "unconnected-(J4-Pad43)") (class "Default")
      (node (ref "J4") (pin "43") (pintype "passive+no_connect"))
    )
    (net (code "213") (name "unconnected-(J4-Pad44)") (class "Default")
      (node (ref "J4") (pin "44") (pintype "passive+no_connect"))
    )
    (net (code "214") (name "unconnected-(J4-Pad45)") (class "Default")
      (node (ref "J4") (pin "45") (pintype "passive+no_connect"))
    )
    (net (code "215") (name "unconnected-(J4-Pad46)") (class "Default")
      (node (ref "J4") (pin "46") (pintype "passive+no_connect"))
    )
    (net (code "216") (name "unconnected-(J4-Pad49)") (class "Default")
      (node (ref "J4") (pin "49") (pintype "passive+no_connect"))
    )
    (net (code "217") (name "unconnected-(J4-Pad50)") (class "Default")
      (node (ref "J4") (pin "50") (pintype "passive+no_connect"))
    )
    (net (code "218") (name "unconnected-(J4-Pad51)") (class "Default")
      (node (ref "J4") (pin "51") (pintype "passive+no_connect"))
    )
    (net (code "219") (name "unconnected-(J4-Pad52)") (class "Default")
      (node (ref "J4") (pin "52") (pintype "passive+no_connect"))
    )
    (net (code "220") (name "unconnected-(J4-Pad55)") (class "Default")
      (node (ref "J4") (pin "55") (pintype "passive+no_connect"))
    )
    (net (code "221") (name "unconnected-(J4-Pad56)") (class "Default")
      (node (ref "J4") (pin "56") (pintype "passive+no_connect"))
    )
    (net (code "222") (name "unconnected-(J4-Pad57)") (class "Default")
      (node (ref "J4") (pin "57") (pintype "passive+no_connect"))
    )
    (net (code "223") (name "unconnected-(J4-Pad58)") (class "Default")
      (node (ref "J4") (pin "58") (pintype "passive+no_connect"))
    )
    (net (code "224") (name "unconnected-(J4-Pad61)") (class "Default")
      (node (ref "J4") (pin "61") (pintype "passive+no_connect"))
    )
    (net (code "225") (name "unconnected-(J4-Pad62)") (class "Default")
      (node (ref "J4") (pin "62") (pintype "passive+no_connect"))
    )
    (net (code "226") (name "unconnected-(J4-Pad63)") (class "Default")
      (node (ref "J4") (pin "63") (pintype "passive+no_connect"))
    )
    (net (code "227") (name "unconnected-(J4-Pad64)") (class "Default")
      (node (ref "J4") (pin "64") (pintype "passive+no_connect"))
    )
    (net (code "228") (name "unconnected-(J4-Pad67)") (class "Default")
      (node (ref "J4") (pin "67") (pintype "passive+no_connect"))
    )
    (net (code "229") (name "unconnected-(J4-Pad68)") (class "Default")
      (node (ref "J4") (pin "68") (pintype "passive+no_connect"))
    )
    (net (code "230") (name "unconnected-(J4-Pad69)") (class "Default")
      (node (ref "J4") (pin "69") (pintype "passive+no_connect"))
    )
    (net (code "231") (name "unconnected-(J4-Pad70)") (class "Default")
      (node (ref "J4") (pin "70") (pintype "passive+no_connect"))
    )
    (net (code "232") (name "unconnected-(J4-Pad73)") (class "Default")
      (node (ref "J4") (pin "73") (pintype "passive+no_connect"))
    )
    (net (code "233") (name "unconnected-(J4-Pad74)") (class "Default")
      (node (ref "J4") (pin "74") (pintype "passive+no_connect"))
    )
    (net (code "234") (name "unconnected-(J4-Pad75)") (class "Default")
      (node (ref "J4") (pin "75") (pintype "passive+no_connect"))
    )
    (net (code "235") (name "unconnected-(J4-Pad76)") (class "Default")
      (node (ref "J4") (pin "76") (pintype "passive+no_connect"))
    )
    (net (code "236") (name "unconnected-(J4-Pad79)") (class "Default")
      (node (ref "J4") (pin "79") (pintype "passive+no_connect"))
    )
    (net (code "237") (name "unconnected-(J4-Pad80)") (class "Default")
      (node (ref "J4") (pin "80") (pintype "passive+no_connect"))
    )
    (net (code "238") (name "unconnected-(J4-Pad81)") (class "Default")
      (node (ref "J4") (pin "81") (pintype "passive+no_connect"))
    )
    (net (code "239") (name "unconnected-(J4-Pad82)") (class "Default")
      (node (ref "J4") (pin "82") (pintype "passive+no_connect"))
    )
    (net (code "240") (name "unconnected-(J4-Pad85)") (class "Default")
      (node (ref "J4") (pin "85") (pintype "passive+no_connect"))
    )
    (net (code "241") (name "unconnected-(J4-Pad86)") (class "Default")
      (node (ref "J4") (pin "86") (pintype "passive+no_connect"))
    )
    (net (code "242") (name "unconnected-(J4-Pad87)") (class "Default")
      (node (ref "J4") (pin "87") (pintype "passive+no_connect"))
    )
    (net (code "243") (name "unconnected-(J4-Pad88)") (class "Default")
      (node (ref "J4") (pin "88") (pintype "passive+no_connect"))
    )
    (net (code "244") (name "unconnected-(J4-Pad91)") (class "Default")
      (node (ref "J4") (pin "91") (pintype "passive+no_connect"))
    )
    (net (code "245") (name "unconnected-(J4-Pad92)") (class "Default")
      (node (ref "J4") (pin "92") (pintype "passive+no_connect"))
    )
    (net (code "246") (name "unconnected-(J4-Pad93)") (class "Default")
      (node (ref "J4") (pin "93") (pintype "passive+no_connect"))
    )
    (net (code "247") (name "unconnected-(J4-Pad94)") (class "Default")
      (node (ref "J4") (pin "94") (pintype "passive+no_connect"))
    )
    (net (code "248") (name "unconnected-(J4-Pad97)") (class "Default")
      (node (ref "J4") (pin "97") (pintype "passive+no_connect"))
    )
    (net (code "249") (name "unconnected-(J4-Pad98)") (class "Default")
      (node (ref "J4") (pin "98") (pintype "passive+no_connect"))
    )
    (net (code "250") (name "unconnected-(J4-Pad99)") (class "Default")
      (node (ref "J4") (pin "99") (pintype "passive+no_connect"))
    )
    (net (code "251") (name "unconnected-(J4-Pad100)") (class "Default")
      (node (ref "J4") (pin "100") (pintype "passive+no_connect"))
    )
    (net (code "252") (name "unconnected-(J4-Pad103)") (class "Default")
      (node (ref "J4") (pin "103") (pintype "passive+no_connect"))
    )
    (net (code "253") (name "unconnected-(J4-Pad104)") (class "Default")
      (node (ref "J4") (pin "104") (pintype "passive+no_connect"))
    )
    (net (code "254") (name "unconnected-(J4-Pad105)") (class "Default")
      (node (ref "J4") (pin "105") (pintype "passive+no_connect"))
    )
    (net (code "255") (name "unconnected-(J4-Pad106)") (class "Default")
      (node (ref "J4") (pin "106") (pintype "passive+no_connect"))
    )
    (net (code "256") (name "unconnected-(J4-Pad109)") (class "Default")
      (node (ref "J4") (pin "109") (pintype "passive+no_connect"))
    )
    (net (code "257") (name "unconnected-(J4-Pad110)") (class "Default")
      (node (ref "J4") (pin "110") (pintype "passive+no_connect"))
    )
    (net (code "258") (name "unconnected-(J4-Pad111)") (class "Default")
      (node (ref "J4") (pin "111") (pintype "passive+no_connect"))
    )
    (net (code "259") (name "unconnected-(J4-Pad112)") (class "Default")
      (node (ref "J4") (pin "112") (pintype "passive+no_connect"))
    )
    (net (code "260") (name "unconnected-(J4-Pad115)") (class "Default")
      (node (ref "J4") (pin "115") (pintype "passive+no_connect"))
    )
    (net (code "261") (name "unconnected-(J4-Pad116)") (class "Default")
      (node (ref "J4") (pin "116") (pintype "passive+no_connect"))
    )
    (net (code "262") (name "unconnected-(J4-Pad117)") (class "Default")
      (node (ref "J4") (pin "117") (pintype "passive+no_connect"))
    )
    (net (code "263") (name "unconnected-(J4-Pad118)") (class "Default")
      (node (ref "J4") (pin "118") (pintype "passive+no_connect"))
    )
    (net (code "264") (name "unconnected-(J4-Pad121)") (class "Default")
      (node (ref "J4") (pin "121") (pintype "passive+no_connect"))
    )
    (net (code "265") (name "unconnected-(J4-Pad122)") (class "Default")
      (node (ref "J4") (pin "122") (pintype "passive+no_connect"))
    )
    (net (code "266") (name "unconnected-(J5-Pad43)") (class "Default")
      (node (ref "J5") (pin "43") (pintype "passive+no_connect"))
    )
    (net (code "267") (name "unconnected-(J5-Pad45)") (class "Default")
      (node (ref "J5") (pin "45") (pintype "passive+no_connect"))
    )
    (net (code "268") (name "unconnected-(J5-Pad49)") (class "Default")
      (node (ref "J5") (pin "49") (pintype "passive+no_connect"))
    )
    (net (code "269") (name "unconnected-(J5-Pad51)") (class "Default")
      (node (ref "J5") (pin "51") (pintype "passive+no_connect"))
    )
    (net (code "270") (name "unconnected-(J5-Pad55)") (class "Default")
      (node (ref "J5") (pin "55") (pintype "passive+no_connect"))
    )
    (net (code "271") (name "unconnected-(J5-Pad57)") (class "Default")
      (node (ref "J5") (pin "57") (pintype "passive+no_connect"))
    )
    (net (code "272") (name "unconnected-(J5-Pad61)") (class "Default")
      (node (ref "J5") (pin "61") (pintype "passive+no_connect"))
    )
    (net (code "273") (name "unconnected-(J5-Pad63)") (class "Default")
      (node (ref "J5") (pin "63") (pintype "passive+no_connect"))
    )
    (net (code "274") (name "unconnected-(J5-Pad67)") (class "Default")
      (node (ref "J5") (pin "67") (pintype "passive+no_connect"))
    )
    (net (code "275") (name "unconnected-(J5-Pad68)") (class "Default")
      (node (ref "J5") (pin "68") (pintype "passive+no_connect"))
    )
    (net (code "276") (name "unconnected-(J5-Pad69)") (class "Default")
      (node (ref "J5") (pin "69") (pintype "passive+no_connect"))
    )
    (net (code "277") (name "unconnected-(J5-Pad70)") (class "Default")
      (node (ref "J5") (pin "70") (pintype "passive+no_connect"))
    )
    (net (code "278") (name "unconnected-(J5-Pad73)") (class "Default")
      (node (ref "J5") (pin "73") (pintype "passive+no_connect"))
    )
    (net (code "279") (name "unconnected-(J5-Pad74)") (class "Default")
      (node (ref "J5") (pin "74") (pintype "passive"))
    )
    (net (code "280") (name "unconnected-(J5-Pad75)") (class "Default")
      (node (ref "J5") (pin "75") (pintype "passive+no_connect"))
    )
    (net (code "281") (name "unconnected-(J5-Pad76)") (class "Default")
      (node (ref "J5") (pin "76") (pintype "passive+no_connect"))
    )
    (net (code "282") (name "unconnected-(J5-Pad79)") (class "Default")
      (node (ref "J5") (pin "79") (pintype "passive+no_connect"))
    )
    (net (code "283") (name "unconnected-(J5-Pad80)") (class "Default")
      (node (ref "J5") (pin "80") (pintype "passive+no_connect"))
    )
    (net (code "284") (name "unconnected-(J5-Pad82)") (class "Default")
      (node (ref "J5") (pin "82") (pintype "passive+no_connect"))
    )
    (net (code "285") (name "unconnected-(J5-Pad85)") (class "Default")
      (node (ref "J5") (pin "85") (pintype "passive+no_connect"))
    )
    (net (code "286") (name "unconnected-(J5-Pad86)") (class "Default")
      (node (ref "J5") (pin "86") (pintype "passive+no_connect"))
    )
    (net (code "287") (name "unconnected-(J5-Pad87)") (class "Default")
      (node (ref "J5") (pin "87") (pintype "passive+no_connect"))
    )
    (net (code "288") (name "unconnected-(J5-Pad88)") (class "Default")
      (node (ref "J5") (pin "88") (pintype "passive+no_connect"))
    )
    (net (code "289") (name "unconnected-(J5-Pad91)") (class "Default")
      (node (ref "J5") (pin "91") (pintype "passive+no_connect"))
    )
    (net (code "290") (name "unconnected-(J5-Pad92)") (class "Default")
      (node (ref "J5") (pin "92") (pintype "passive+no_connect"))
    )
    (net (code "291") (name "unconnected-(J5-Pad93)") (class "Default")
      (node (ref "J5") (pin "93") (pintype "passive+no_connect"))
    )
    (net (code "292") (name "unconnected-(J5-Pad94)") (class "Default")
      (node (ref "J5") (pin "94") (pintype "passive+no_connect"))
    )
    (net (code "293") (name "unconnected-(J5-Pad97)") (class "Default")
      (node (ref "J5") (pin "97") (pintype "passive+no_connect"))
    )
    (net (code "294") (name "unconnected-(J5-Pad98)") (class "Default")
      (node (ref "J5") (pin "98") (pintype "passive+no_connect"))
    )
    (net (code "295") (name "unconnected-(J5-Pad99)") (class "Default")
      (node (ref "J5") (pin "99") (pintype "passive+no_connect"))
    )
    (net (code "296") (name "unconnected-(J5-Pad100)") (class "Default")
      (node (ref "J5") (pin "100") (pintype "passive+no_connect"))
    )
    (net (code "297") (name "unconnected-(J5-Pad103)") (class "Default")
      (node (ref "J5") (pin "103") (pintype "passive+no_connect"))
    )
    (net (code "298") (name "unconnected-(J5-Pad104)") (class "Default")
      (node (ref "J5") (pin "104") (pintype "passive+no_connect"))
    )
    (net (code "299") (name "unconnected-(J5-Pad105)") (class "Default")
      (node (ref "J5") (pin "105") (pintype "passive+no_connect"))
    )
    (net (code "300") (name "unconnected-(J5-Pad106)") (class "Default")
      (node (ref "J5") (pin "106") (pintype "passive+no_connect"))
    )
    (net (code "301") (name "unconnected-(J5-Pad109)") (class "Default")
      (node (ref "J5") (pin "109") (pintype "passive+no_connect"))
    )
    (net (code "302") (name "unconnected-(J5-Pad110)") (class "Default")
      (node (ref "J5") (pin "110") (pintype "passive+no_connect"))
    )
    (net (code "303") (name "unconnected-(J5-Pad111)") (class "Default")
      (node (ref "J5") (pin "111") (pintype "passive+no_connect"))
    )
    (net (code "304") (name "unconnected-(J5-Pad112)") (class "Default")
      (node (ref "J5") (pin "112") (pintype "passive+no_connect"))
    )
    (net (code "305") (name "unconnected-(J5-Pad116)") (class "Default")
      (node (ref "J5") (pin "116") (pintype "passive+no_connect"))
    )
    (net (code "306") (name "unconnected-(J5-Pad118)") (class "Default")
      (node (ref "J5") (pin "118") (pintype "passive+no_connect"))
    )
    (net (code "307") (name "unconnected-(J5-Pad121)") (class "Default")
      (node (ref "J5") (pin "121") (pintype "passive+no_connect"))
    )
    (net (code "308") (name "unconnected-(J5-Pad122)") (class "Default")
      (node (ref "J5") (pin "122") (pintype "passive+no_connect"))
    )
    (net (code "309") (name "unconnected-(J6-Pad21)") (class "Default")
      (node (ref "J6") (pin "21") (pintype "passive+no_connect"))
    )
    (net (code "310") (name "unconnected-(J6-Pad38)") (class "Default")
      (node (ref "J6") (pin "38") (pintype "passive+no_connect"))
    )
    (net (code "311") (name "unconnected-(J6-Pad44)") (class "Default")
      (node (ref "J6") (pin "44") (pintype "passive+no_connect"))
    )
    (net (code "312") (name "unconnected-(J6-Pad46)") (class "Default")
      (node (ref "J6") (pin "46") (pintype "passive+no_connect"))
    )
    (net (code "313") (name "unconnected-(J6-Pad50)") (class "Default")
      (node (ref "J6") (pin "50") (pintype "passive+no_connect"))
    )
    (net (code "314") (name "unconnected-(J6-Pad52)") (class "Default")
      (node (ref "J6") (pin "52") (pintype "passive+no_connect"))
    )
    (net (code "315") (name "unconnected-(J6-Pad56)") (class "Default")
      (node (ref "J6") (pin "56") (pintype "passive+no_connect"))
    )
    (net (code "316") (name "unconnected-(J6-Pad58)") (class "Default")
      (node (ref "J6") (pin "58") (pintype "passive+no_connect"))
    )
    (net (code "317") (name "unconnected-(J6-Pad64)") (class "Default")
      (node (ref "J6") (pin "64") (pintype "passive+no_connect"))
    )
    (net (code "318") (name "unconnected-(J6-Pad68)") (class "Default")
      (node (ref "J6") (pin "68") (pintype "passive+no_connect"))
    )
    (net (code "319") (name "unconnected-(J6-Pad70)") (class "Default")
      (node (ref "J6") (pin "70") (pintype "passive+no_connect"))
    )
    (net (code "320") (name "unconnected-(J6-Pad93)") (class "Default")
      (node (ref "J6") (pin "93") (pintype "passive+no_connect"))
    )
    (net (code "321") (name "unconnected-(J6-Pad121)") (class "Default")
      (node (ref "J6") (pin "121") (pintype "passive+no_connect"))
    )
    (net (code "322") (name "unconnected-(J6-Pad122)") (class "Default")
      (node (ref "J6") (pin "122") (pintype "passive+no_connect"))
    )
  )
)
